# ETH_RJ45wLED.net
KiCad netlist of a schematic drawn in Altium Designer
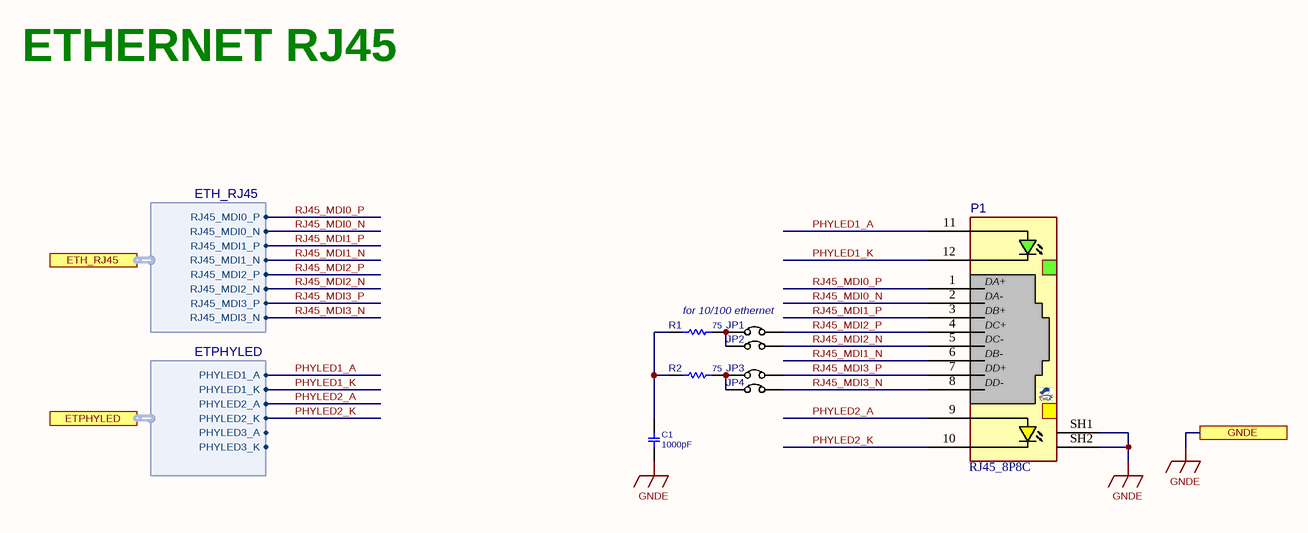
[diagram p0: ETH_RJ45wLED.SchDoc]

(export (version "E")
  (design (tool "Eeschema 10.0.6"))
  (components
    (comp (ref "C1")
      (value "1000pF")
      (footprint "C1206")
      (description "CAP, MLCC")
      (fields (field (name "MANF_P#") "1206B102K202NT"))
      (libsource (lib "mlcc_smd_passive") (part "CAP_SMD_MLCC_22n50V"))
    )
    (comp (ref "JP1")
      (value "JMPSOLDER")
      (footprint "JP_30X50")
      (description "JUMPER, HEADER 2PIN")
      (fields (field (name "MANF") "MANF") (field (name "MANF_P#") "MANF_P#"))
      (libsource (lib "test-tp_jumper") (part "JUMPER_SOLDER"))
    )
    (comp (ref "JP2")
      (value "JMPSOLDER")
      (footprint "JP_30X50")
      (description "JUMPER, HEADER 2PIN")
      (fields (field (name "MANF") "MANF") (field (name "MANF_P#") "MANF_P#"))
      (libsource (lib "test-tp_jumper") (part "JUMPER_SOLDER"))
    )
    (comp (ref "JP3")
      (value "JMPSOLDER")
      (footprint "JP_30X50")
      (description "JUMPER, HEADER 2PIN")
      (fields (field (name "MANF") "MANF") (field (name "MANF_P#") "MANF_P#"))
      (libsource (lib "test-tp_jumper") (part "JUMPER_SOLDER"))
    )
    (comp (ref "JP4")
      (value "JMPSOLDER")
      (footprint "JP_30X50")
      (description "JUMPER, HEADER 2PIN")
      (fields (field (name "MANF") "MANF") (field (name "MANF_P#") "MANF_P#"))
      (libsource (lib "test-tp_jumper") (part "JUMPER_SOLDER"))
    )
    (comp (ref "P1")
      (value "RJ45_8P8C")
      (footprint "RJ45_8S_RA_TU_L")
      (description "RJ45, 8P+LED, SHIELDED, RightAngle, TabUP")
      (fields (field (name "MANF") "WURTH") (field (name "MANF_P#") "615008137421"))
      (libsource (lib "conn_rj_ModularJack") (part "RJ45_8S_RA_TU_L"))
    )
    (comp (ref "R1")
      (value "75")
      (footprint "R0603O")
      (description "RESISTOR, SMD, THICK FILM, YAGEO")
      (fields (field (name "MANF_P#") "RC0402FR-071KL") (field (name "MANF") "Yageo"))
      (libsource (lib "res_smd_Yageo0402_thickfilm") (part "RES_SMD_1K_0402YK"))
    )
    (comp (ref "R2")
      (value "75")
      (footprint "R0603O")
      (description "RESISTOR, SMD, THICK FILM, YAGEO")
      (fields (field (name "MANF_P#") "RC0402FR-071KL") (field (name "MANF") "Yageo"))
      (libsource (lib "res_smd_Yageo0402_thickfilm") (part "RES_SMD_1K_0402YK"))
    )
  )
  (nets
    (net (code "3") (name "/PHYLED1_A") (class "Default")
      (node (ref "P1") (pin "11") (pinfunction "GLED+_11") (pintype "passive"))
    )
    (net (code "4") (name "/PHYLED1_K") (class "Default")
      (node (ref "P1") (pin "12") (pinfunction "GLED-_12") (pintype "passive"))
    )
    (net (code "5") (name "/PHYLED2_A") (class "Default")
      (node (ref "P1") (pin "9") (pinfunction "YLED+_9") (pintype "passive"))
    )
    (net (code "6") (name "/PHYLED2_K") (class "Default")
      (node (ref "P1") (pin "10") (pinfunction "YLED-_10") (pintype "passive"))
    )
    (net (code "7") (name "/RJ45_MDI0_N") (class "Default")
      (node (ref "P1") (pin "2") (pinfunction "DA-_2") (pintype "passive"))
    )
    (net (code "8") (name "/RJ45_MDI0_P") (class "Default")
      (node (ref "P1") (pin "1") (pinfunction "DA+_1") (pintype "passive"))
    )
    (net (code "9") (name "/RJ45_MDI1_N") (class "Default")
      (node (ref "P1") (pin "6") (pinfunction "DB-_6") (pintype "passive"))
    )
    (net (code "10") (name "/RJ45_MDI1_P") (class "Default")
      (node (ref "P1") (pin "3") (pinfunction "DB+_3") (pintype "passive"))
    )
    (net (code "11") (name "/RJ45_MDI2_N") (class "Default")
      (node (ref "JP2") (pin "2") (pinfunction "2_2") (pintype "passive"))
      (node (ref "P1") (pin "5") (pinfunction "DC-_5") (pintype "passive"))
    )
    (net (code "12") (name "/RJ45_MDI2_P") (class "Default")
      (node (ref "JP1") (pin "2") (pinfunction "2_2") (pintype "passive"))
      (node (ref "P1") (pin "4") (pinfunction "DC+_4") (pintype "passive"))
    )
    (net (code "13") (name "/RJ45_MDI3_N") (class "Default")
      (node (ref "JP4") (pin "2") (pinfunction "2_2") (pintype "passive"))
      (node (ref "P1") (pin "8") (pinfunction "DD-_8") (pintype "passive"))
    )
    (net (code "14") (name "/RJ45_MDI3_P") (class "Default")
      (node (ref "JP3") (pin "2") (pinfunction "2_2") (pintype "passive"))
      (node (ref "P1") (pin "7") (pinfunction "DD+_7") (pintype "passive"))
    )
    (net (code "17") (name "GNDE") (class "Default")
      (node (ref "C1") (pin "2") (pinfunction "2_2") (pintype "passive"))
      (node (ref "P1") (pin "SH1") (pinfunction "SH1_SH1") (pintype "passive"))
      (node (ref "P1") (pin "SH2") (pinfunction "SH2_SH2") (pintype "passive"))
    )
    (net (code "18") (name "Net-(C1-Pad1)") (class "Default")
      (node (ref "C1") (pin "1") (pinfunction "1_1") (pintype "passive"))
      (node (ref "R1") (pin "1") (pinfunction "1_1") (pintype "passive"))
      (node (ref "R2") (pin "1") (pinfunction "1_1") (pintype "passive"))
    )
    (net (code "19") (name "Net-(JP1-Pad1)") (class "Default")
      (node (ref "JP1") (pin "1") (pinfunction "1_1") (pintype "passive"))
      (node (ref "JP2") (pin "1") (pinfunction "1_1") (pintype "passive"))
      (node (ref "R1") (pin "2") (pinfunction "2_2") (pintype "passive"))
    )
    (net (code "20") (name "Net-(JP3-Pad1)") (class "Default")
      (node (ref "JP3") (pin "1") (pinfunction "1_1") (pintype "passive"))
      (node (ref "JP4") (pin "1") (pinfunction "1_1") (pintype "passive"))
      (node (ref "R2") (pin "2") (pinfunction "2_2") (pintype "passive"))
    )
  )
)
